# CocoBra.net
KiCad netlist of a schematic drawn in EAGLE
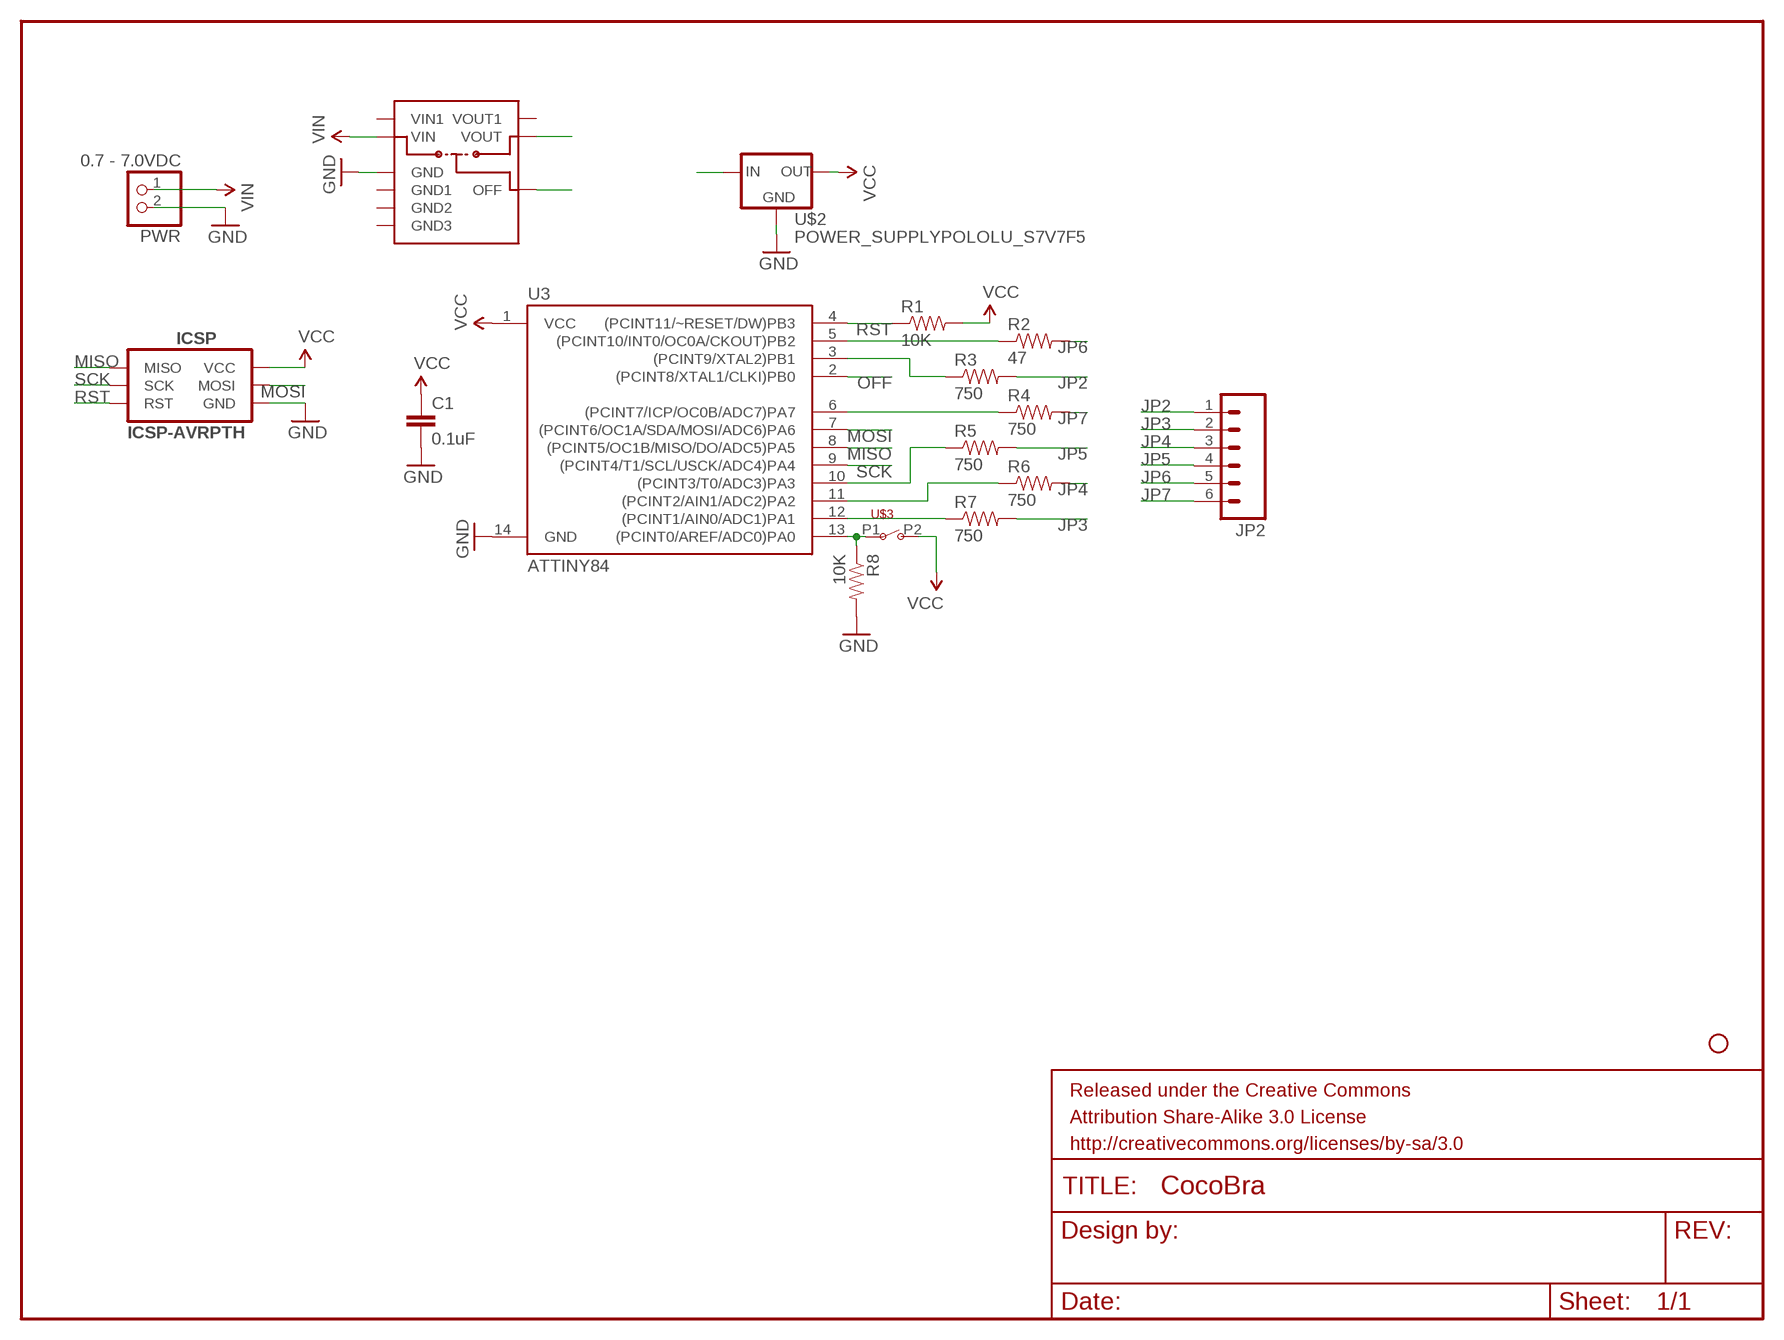
[diagram p0: schematic, sheet 1]

(export (version "E")
  (design (tool "Eeschema 10.0.6"))
  (components
    (comp (ref "C1")
      (value "0.1uF")
      (footprint "eagle-import:CAP-PTH-SMALL2")
      (libsource (lib "eagle-import") (part "CAPPTH2"))
    )
    (comp (ref "FRAME1")
      (value "FRAME-LETTER")
      (footprint "eagle-import:CREATIVE_COMMONS")
      (libsource (lib "eagle-import") (part "FRAME-LETTER"))
    )
    (comp (ref "ICSP")
      (value "ICSP-AVRPTH")
      (footprint "eagle-import:2X3-SHROUDED")
      (libsource (lib "eagle-import") (part "ICSP-AVRPTH"))
    )
    (comp (ref "JP2")
      (value "M06SIP")
      (footprint "eagle-import:1X06")
      (libsource (lib "eagle-import") (part "M06SIP"))
    )
    (comp (ref "PWR")
      (value "0.7 - 7.0VDC")
      (footprint "eagle-import:JST-PH-2-THM-RA")
      (libsource (lib "eagle-import") (part "JST_2PIN-THM-RA"))
    )
    (comp (ref "R1")
      (value "10K")
      (footprint "eagle-import:AXIAL-0.2")
      (libsource (lib "eagle-import") (part "RESISTORAXIAL-0.2"))
    )
    (comp (ref "R2")
      (value "47")
      (footprint "eagle-import:AXIAL-0.3")
      (libsource (lib "eagle-import") (part "RESISTORAXIAL-0.3"))
    )
    (comp (ref "R3")
      (value "750")
      (footprint "eagle-import:AXIAL-0.3")
      (libsource (lib "eagle-import") (part "RESISTORAXIAL-0.3"))
    )
    (comp (ref "R4")
      (value "750")
      (footprint "eagle-import:AXIAL-0.3")
      (libsource (lib "eagle-import") (part "RESISTORAXIAL-0.3"))
    )
    (comp (ref "R5")
      (value "750")
      (footprint "eagle-import:AXIAL-0.3")
      (libsource (lib "eagle-import") (part "RESISTORAXIAL-0.3"))
    )
    (comp (ref "R6")
      (value "750")
      (footprint "eagle-import:AXIAL-0.3")
      (libsource (lib "eagle-import") (part "RESISTORAXIAL-0.3"))
    )
    (comp (ref "R7")
      (value "750")
      (footprint "eagle-import:AXIAL-0.3")
      (libsource (lib "eagle-import") (part "RESISTORAXIAL-0.3"))
    )
    (comp (ref "R8")
      (value "10K")
      (footprint "eagle-import:AXIAL-0.2")
      (libsource (lib "eagle-import") (part "RESISTORAXIAL-0.2"))
    )
    (comp (ref "STANDOFF3")
      (value "STAND-OFF#2")
      (footprint "eagle-import:STAND-OFF-#2")
      (libsource (lib "eagle-import") (part "STAND-OFF#2"))
    )
    (comp (ref "U$2")
      (value "POWER_SUPPLYPOLOLU_S7V7F5")
      (footprint "eagle-import:POLOLU_POWER_SUPPLY_S7V7F5")
      (libsource (lib "eagle-import") (part "POWER_SUPPLYPOLOLU_S7V7F5"))
    )
    (comp (ref "U$3")
      (value "SWITCH-SPSTTILT")
      (footprint "eagle-import:SWITCH-SPST-TILT")
      (libsource (lib "eagle-import") (part "SWITCH-SPSTTILT"))
    )
    (comp (ref "U$4")
      (value "POLOLU_POWER_SWITCHPTH")
      (footprint "eagle-import:POLOLU_POWER_SWITCH")
      (libsource (lib "eagle-import") (part "POLOLU_POWER_SWITCHPTH"))
    )
    (comp (ref "U3")
      (value "ATTINY84")
      (footprint "eagle-import:DIL14")
      (libsource (lib "eagle-import") (part "ATTINY84DIL14"))
    )
  )
  (nets
    (net (code "1") (name "/JP2") (class "Default")
      (node (ref "JP2") (pin "1") (pinfunction "1_1") (pintype "passive"))
      (node (ref "R3") (pin "P$2") (pinfunction "2_P$2") (pintype "passive"))
    )
    (net (code "2") (name "/JP3") (class "Default")
      (node (ref "JP2") (pin "2") (pinfunction "2_2") (pintype "passive"))
      (node (ref "R7") (pin "P$2") (pinfunction "2_P$2") (pintype "passive"))
    )
    (net (code "3") (name "/JP4") (class "Default")
      (node (ref "JP2") (pin "3") (pinfunction "3_3") (pintype "passive"))
      (node (ref "R6") (pin "P$2") (pinfunction "2_P$2") (pintype "passive"))
    )
    (net (code "4") (name "/JP5") (class "Default")
      (node (ref "JP2") (pin "4") (pinfunction "4_4") (pintype "passive"))
      (node (ref "R5") (pin "P$2") (pinfunction "2_P$2") (pintype "passive"))
    )
    (net (code "5") (name "/JP6") (class "Default")
      (node (ref "JP2") (pin "5") (pinfunction "5_5") (pintype "passive"))
      (node (ref "R2") (pin "P$2") (pinfunction "2_P$2") (pintype "passive"))
    )
    (net (code "6") (name "/JP7") (class "Default")
      (node (ref "JP2") (pin "6") (pinfunction "6_6") (pintype "passive"))
      (node (ref "R4") (pin "P$2") (pinfunction "2_P$2") (pintype "passive"))
    )
    (net (code "7") (name "/MISO") (class "Default")
      (node (ref "ICSP") (pin "1") (pinfunction "MISO_1") (pintype "bidirectional"))
      (node (ref "U3") (pin "8") (pinfunction "(PCINT5/OC1B/MISO/DO/ADC5)PA5_8") (pintype "bidirectional"))
    )
    (net (code "8") (name "/MOSI") (class "Default")
      (node (ref "ICSP") (pin "4") (pinfunction "MOSI_4") (pintype "bidirectional"))
      (node (ref "U3") (pin "7") (pinfunction "(PCINT6/OC1A/SDA/MOSI/ADC6)PA6_7") (pintype "bidirectional"))
    )
    (net (code "9") (name "/OFF") (class "Default")
      (node (ref "U$4") (pin "OFF") (pinfunction "OFF_OFF") (pintype "bidirectional"))
      (node (ref "U3") (pin "2") (pinfunction "(PCINT8/XTAL1/CLKI)PB0_2") (pintype "bidirectional"))
    )
    (net (code "10") (name "/RST") (class "Default")
      (node (ref "ICSP") (pin "5") (pinfunction "RST_5") (pintype "bidirectional"))
      (node (ref "R1") (pin "P$1") (pinfunction "1_P$1") (pintype "passive"))
      (node (ref "U3") (pin "4") (pinfunction "(PCINT11/~{RESET/DW})PB3_4") (pintype "bidirectional"))
    )
    (net (code "11") (name "/SCK") (class "Default")
      (node (ref "ICSP") (pin "3") (pinfunction "SCK_3") (pintype "bidirectional"))
      (node (ref "U3") (pin "9") (pinfunction "(PCINT4/T1/SCL/USCK/ADC4)PA4_9") (pintype "bidirectional"))
    )
    (net (code "12") (name "/VOUT") (class "Default")
      (node (ref "U$2") (pin "VIN") (pinfunction "IN_VIN") (pintype "input"))
      (node (ref "U$4") (pin "VOUT") (pinfunction "VOUT_VOUT") (pintype "bidirectional"))
    )
    (net (code "13") (name "GND") (class "Default")
      (node (ref "C1") (pin "2") (pinfunction "2_2") (pintype "passive"))
      (node (ref "ICSP") (pin "6") (pinfunction "GND_6") (pintype "bidirectional"))
      (node (ref "PWR") (pin "2") (pinfunction "1_2") (pintype "passive"))
      (node (ref "R8") (pin "P$2") (pinfunction "2_P$2") (pintype "passive"))
      (node (ref "U$2") (pin "GND") (pinfunction "GND_GND") (pintype "input"))
      (node (ref "U$4") (pin "GND") (pinfunction "GND_GND") (pintype "bidirectional"))
      (node (ref "U3") (pin "14") (pinfunction "GND_14") (pintype "bidirectional"))
    )
    (net (code "14") (name "Net-(R2-1)") (class "Default")
      (node (ref "R2") (pin "P$1") (pinfunction "1_P$1") (pintype "passive"))
      (node (ref "U3") (pin "5") (pinfunction "(PCINT10/INT0/OC0A/CKOUT)PB2_5") (pintype "bidirectional"))
    )
    (net (code "15") (name "Net-(R3-1)") (class "Default")
      (node (ref "R3") (pin "P$1") (pinfunction "1_P$1") (pintype "passive"))
      (node (ref "U3") (pin "3") (pinfunction "(PCINT9/XTAL2)PB1_3") (pintype "bidirectional"))
    )
    (net (code "16") (name "Net-(R4-1)") (class "Default")
      (node (ref "R4") (pin "P$1") (pinfunction "1_P$1") (pintype "passive"))
      (node (ref "U3") (pin "6") (pinfunction "(PCINT7/ICP/OC0B/ADC7)PA7_6") (pintype "bidirectional"))
    )
    (net (code "17") (name "Net-(R5-1)") (class "Default")
      (node (ref "R5") (pin "P$1") (pinfunction "1_P$1") (pintype "passive"))
      (node (ref "U3") (pin "10") (pinfunction "(PCINT3/T0/ADC3)PA3_10") (pintype "bidirectional"))
    )
    (net (code "18") (name "Net-(R6-1)") (class "Default")
      (node (ref "R6") (pin "P$1") (pinfunction "1_P$1") (pintype "passive"))
      (node (ref "U3") (pin "11") (pinfunction "(PCINT2/AIN1/ADC2)PA2_11") (pintype "bidirectional"))
    )
    (net (code "19") (name "Net-(R7-1)") (class "Default")
      (node (ref "R7") (pin "P$1") (pinfunction "1_P$1") (pintype "passive"))
      (node (ref "U3") (pin "12") (pinfunction "(PCINT1/AIN0/ADC1)PA1_12") (pintype "bidirectional"))
    )
    (net (code "20") (name "Net-(R8-1)") (class "Default")
      (node (ref "R8") (pin "P$1") (pinfunction "1_P$1") (pintype "passive"))
      (node (ref "U$3") (pin "P1") (pinfunction "P1_P1") (pintype "bidirectional"))
      (node (ref "U3") (pin "13") (pinfunction "(PCINT0/AREF/ADC0)PA0_13") (pintype "bidirectional"))
    )
    (net (code "21") (name "VCC") (class "Default")
      (node (ref "C1") (pin "1") (pinfunction "1_1") (pintype "passive"))
      (node (ref "ICSP") (pin "2") (pinfunction "VCC_2") (pintype "bidirectional"))
      (node (ref "R1") (pin "P$2") (pinfunction "2_P$2") (pintype "passive"))
      (node (ref "U$2") (pin "VOUT") (pinfunction "OUT_VOUT") (pintype "output"))
      (node (ref "U$3") (pin "P2") (pinfunction "P2_P2") (pintype "bidirectional"))
      (node (ref "U3") (pin "1") (pinfunction "VCC_1") (pintype "bidirectional"))
    )
    (net (code "22") (name "VIN") (class "Default")
      (node (ref "PWR") (pin "1") (pinfunction "2_1") (pintype "passive"))
      (node (ref "U$4") (pin "VIN") (pinfunction "VIN_VIN") (pintype "bidirectional"))
    )
    (net (code "23") (name "unconnected-(U$4-PadGND1)") (class "Default")
      (node (ref "U$4") (pin "GND1") (pinfunction "GND1_GND1") (pintype "bidirectional"))
    )
    (net (code "24") (name "unconnected-(U$4-PadGND2)") (class "Default")
      (node (ref "U$4") (pin "GND2") (pinfunction "GND2_GND2") (pintype "bidirectional"))
    )
    (net (code "25") (name "unconnected-(U$4-PadGND3)") (class "Default")
      (node (ref "U$4") (pin "GND3") (pinfunction "GND3_GND3") (pintype "bidirectional"))
    )
    (net (code "26") (name "unconnected-(U$4-PadVIN1)") (class "Default")
      (node (ref "U$4") (pin "VIN1") (pinfunction "VIN1_VIN1") (pintype "bidirectional"))
    )
    (net (code "27") (name "unconnected-(U$4-PadVOUT1)") (class "Default")
      (node (ref "U$4") (pin "VOUT1") (pinfunction "VOUT1_VOUT1") (pintype "bidirectional"))
    )
  )
)
